# RC522.net
KiCad netlist of a schematic drawn in Altium Designer
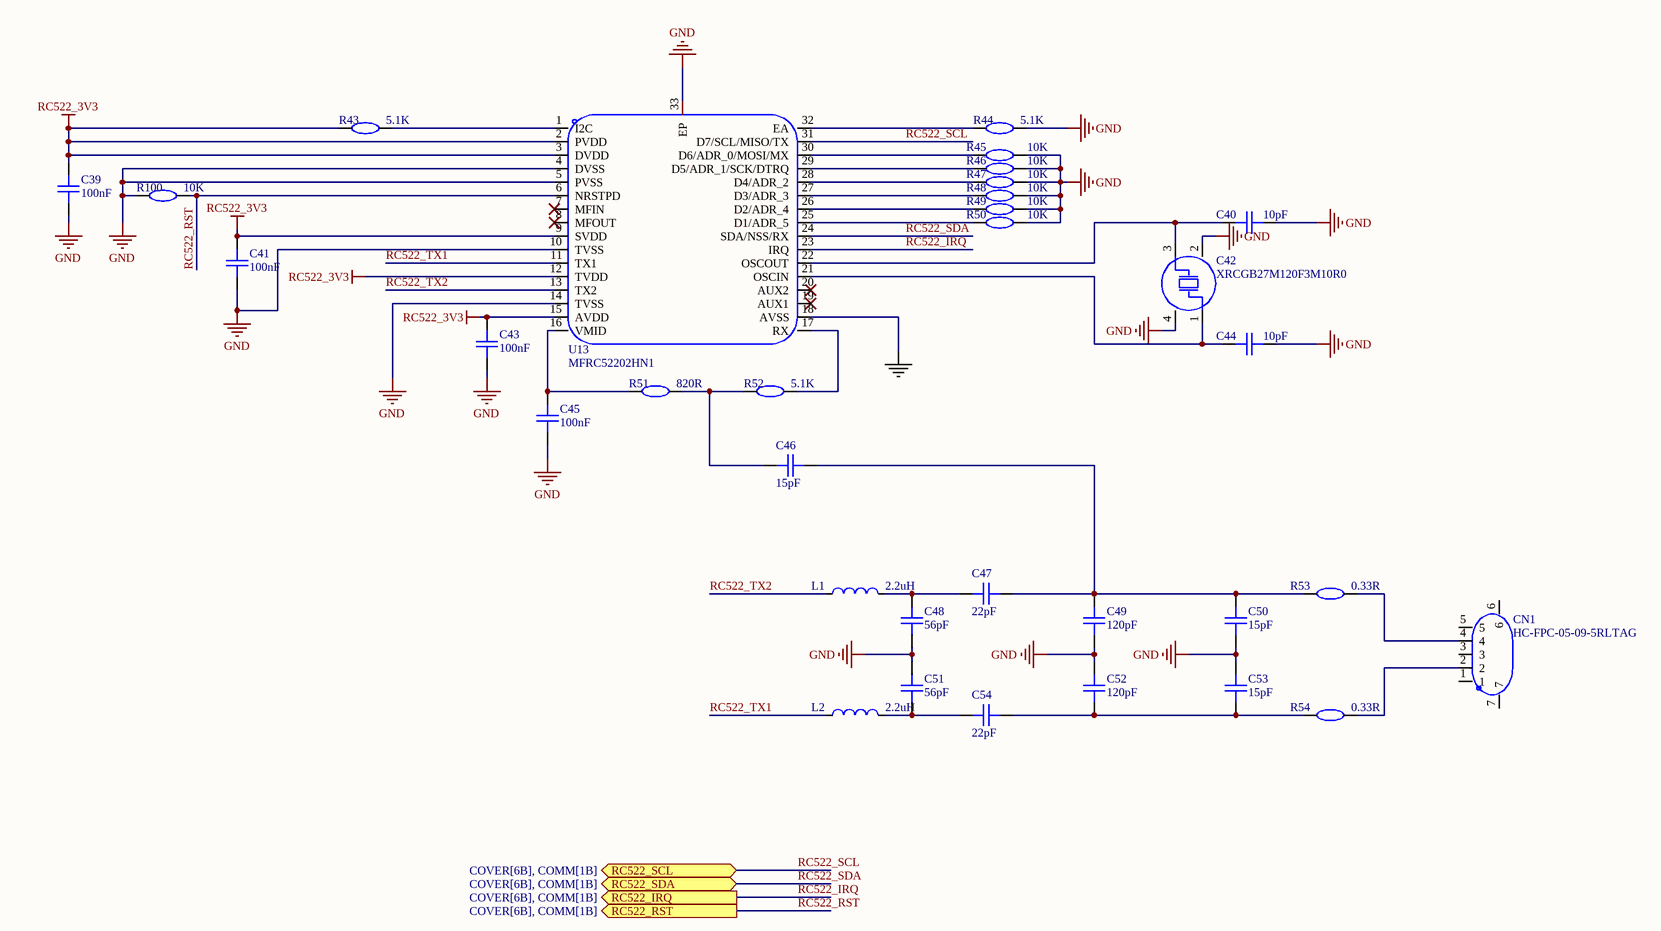
[diagram p0: RC522.SchDoc]

(export (version "E")
  (design (tool "Eeschema 10.0.6"))
  (components
    (comp (ref "C39")
      (value "100nF")
      (footprint "C0402")
      (fields (field (name "NAME") "100nF"))
      (libsource (lib "my_library") (part "CAP_0402"))
    )
    (comp (ref "C40")
      (value "10pF")
      (footprint "C0402")
      (fields (field (name "NAME") "10pF"))
      (libsource (lib "my_library") (part "CAP_0402"))
    )
    (comp (ref "C41")
      (value "100nF")
      (footprint "C0402")
      (fields (field (name "NAME") "100nF"))
      (libsource (lib "my_library") (part "CAP_0402"))
    )
    (comp (ref "C42")
      (value "XRCGB27M120F3M10R0")
      (footprint "CRYSTAL-SMD_4P-L2.0-W1.6-BL-B")
      (fields (field (name "NAME") "XRCGB27M120F3M10R0"))
      (libsource (lib "my_library") (part "XRCGB27M120F3M10R0"))
    )
    (comp (ref "C43")
      (value "100nF")
      (footprint "C0402")
      (fields (field (name "NAME") "100nF"))
      (libsource (lib "my_library") (part "CAP_0402"))
    )
    (comp (ref "C44")
      (value "10pF")
      (footprint "C0402")
      (fields (field (name "NAME") "10pF"))
      (libsource (lib "my_library") (part "CAP_0402"))
    )
    (comp (ref "C45")
      (value "100nF")
      (footprint "C0402")
      (fields (field (name "NAME") "100nF"))
      (libsource (lib "my_library") (part "CAP_0402"))
    )
    (comp (ref "C46")
      (value "15pF")
      (footprint "C0402")
      (fields (field (name "NAME") "15pF"))
      (libsource (lib "my_library") (part "CAP_0402"))
    )
    (comp (ref "C47")
      (value "22pF")
      (footprint "C0402")
      (fields (field (name "NAME") "22pF"))
      (libsource (lib "my_library") (part "CAP_0402"))
    )
    (comp (ref "C48")
      (value "56pF")
      (footprint "C0402")
      (fields (field (name "NAME") "56pF"))
      (libsource (lib "my_library") (part "CAP_0402"))
    )
    (comp (ref "C49")
      (value "120pF")
      (footprint "C0402")
      (fields (field (name "NAME") "120pF"))
      (libsource (lib "my_library") (part "CAP_0402"))
    )
    (comp (ref "C50")
      (value "15pF")
      (footprint "C0402")
      (fields (field (name "NAME") "15pF"))
      (libsource (lib "my_library") (part "CAP_0402"))
    )
    (comp (ref "C51")
      (value "56pF")
      (footprint "C0402")
      (fields (field (name "NAME") "56pF"))
      (libsource (lib "my_library") (part "CAP_0402"))
    )
    (comp (ref "C52")
      (value "120pF")
      (footprint "C0402")
      (fields (field (name "NAME") "120pF"))
      (libsource (lib "my_library") (part "CAP_0402"))
    )
    (comp (ref "C53")
      (value "15pF")
      (footprint "C0402")
      (fields (field (name "NAME") "15pF"))
      (libsource (lib "my_library") (part "CAP_0402"))
    )
    (comp (ref "C54")
      (value "22pF")
      (footprint "C0402")
      (fields (field (name "NAME") "22pF"))
      (libsource (lib "my_library") (part "CAP_0402"))
    )
    (comp (ref "CN1")
      (value "HC-FPC-05-09-5RLTAG")
      (footprint "CONN-SMD_5P-P0.50_HCTL_HC-FPC-05-09-5RLTAG")
      (fields (field (name "MANUFACTURER") "HCTL(华灿天禄)") (field (name "NAME") "HC-FPC-05-09-5RLTAG"))
      (libsource (lib "my_library") (part "HC-FPC-05-09-5RLTAG"))
    )
    (comp (ref "L1")
      (value "2.2uH")
      (footprint "L0603")
      (fields (field (name "NAME") "2.2uH"))
      (libsource (lib "my_library") (part "L_0603"))
    )
    (comp (ref "L2")
      (value "2.2uH")
      (footprint "L0603")
      (fields (field (name "NAME") "2.2uH"))
      (libsource (lib "my_library") (part "L_0603"))
    )
    (comp (ref "R43")
      (value "5.1K")
      (footprint "R0402")
      (fields (field (name "NAME") "5.1K"))
      (libsource (lib "my_library") (part "Res_0402"))
    )
    (comp (ref "R44")
      (value "5.1K")
      (footprint "R0402")
      (fields (field (name "NAME") "5.1K"))
      (libsource (lib "my_library") (part "Res_0402"))
    )
    (comp (ref "R45")
      (value "10K")
      (footprint "R0402")
      (fields (field (name "NAME") "10K"))
      (libsource (lib "my_library") (part "Res_0402"))
    )
    (comp (ref "R46")
      (value "10K")
      (footprint "R0402")
      (fields (field (name "NAME") "10K"))
      (libsource (lib "my_library") (part "Res_0402"))
    )
    (comp (ref "R47")
      (value "10K")
      (footprint "R0402")
      (fields (field (name "NAME") "10K"))
      (libsource (lib "my_library") (part "Res_0402"))
    )
    (comp (ref "R48")
      (value "10K")
      (footprint "R0402")
      (fields (field (name "NAME") "10K"))
      (libsource (lib "my_library") (part "Res_0402"))
    )
    (comp (ref "R49")
      (value "10K")
      (footprint "R0402")
      (fields (field (name "NAME") "10K"))
      (libsource (lib "my_library") (part "Res_0402"))
    )
    (comp (ref "R50")
      (value "10K")
      (footprint "R0402")
      (fields (field (name "NAME") "10K"))
      (libsource (lib "my_library") (part "Res_0402"))
    )
    (comp (ref "R51")
      (value "820R")
      (footprint "R0402")
      (fields (field (name "NAME") "820R"))
      (libsource (lib "my_library") (part "Res_0402"))
    )
    (comp (ref "R52")
      (value "5.1K")
      (footprint "R0402")
      (fields (field (name "NAME") "5.1K"))
      (libsource (lib "my_library") (part "Res_0402"))
    )
    (comp (ref "R53")
      (value "0.33R")
      (footprint "R0402")
      (fields (field (name "NAME") "0.33R"))
      (libsource (lib "my_library") (part "Res_0402"))
    )
    (comp (ref "R54")
      (value "0.33R")
      (footprint "R0402")
      (fields (field (name "NAME") "0.33R"))
      (libsource (lib "my_library") (part "Res_0402"))
    )
    (comp (ref "R100")
      (value "10K")
      (footprint "R0402")
      (fields (field (name "NAME") "10K"))
      (libsource (lib "my_library") (part "Res_0402"))
    )
    (comp (ref "U13")
      (value "MFRC52202HN1")
      (footprint "HVQFN-32_L5.0-W5.0-P0.50-TL-EP3.1")
      (fields (field (name "MANUFACTURER") "NXP(恩智浦)") (field (name "NAME") "MFRC52202HN1"))
      (libsource (lib "my_library") (part "MFRC52202HN1"))
    )
  )
  (nets
    (net (code "1") (name "/RC522_IRQ") (class "Default")
      (node (ref "U13") (pin "23") (pinfunction "IRQ_23") (pintype "passive"))
    )
    (net (code "2") (name "/RC522_RST") (class "Default")
      (node (ref "R100") (pin "2") (pinfunction "2_2") (pintype "passive"))
      (node (ref "U13") (pin "6") (pinfunction "NRSTPD_6") (pintype "passive"))
    )
    (net (code "3") (name "/RC522_SCL") (class "Default")
      (node (ref "U13") (pin "31") (pinfunction "D7/SCL/MISO/TX_31") (pintype "passive"))
    )
    (net (code "4") (name "/RC522_SDA") (class "Default")
      (node (ref "U13") (pin "24") (pinfunction "SDA/NSS/RX_24") (pintype "passive"))
    )
    (net (code "5") (name "/RC522_TX1") (class "Default")
      (node (ref "L2") (pin "1") (pinfunction "1_1") (pintype "passive"))
      (node (ref "U13") (pin "11") (pinfunction "TX1_11") (pintype "passive"))
    )
    (net (code "6") (name "/RC522_TX2") (class "Default")
      (node (ref "L1") (pin "1") (pinfunction "1_1") (pintype "passive"))
      (node (ref "U13") (pin "13") (pinfunction "TX2_13") (pintype "passive"))
    )
    (net (code "7") (name "GND") (class "Default")
      (node (ref "C39") (pin "1") (pinfunction "1_1") (pintype "passive"))
      (node (ref "C40") (pin "1") (pinfunction "1_1") (pintype "passive"))
      (node (ref "C41") (pin "1") (pinfunction "1_1") (pintype "passive"))
      (node (ref "C42") (pin "2") (pinfunction "GND_2") (pintype "passive"))
      (node (ref "C42") (pin "4") (pinfunction "GND_4") (pintype "passive"))
      (node (ref "C43") (pin "1") (pinfunction "1_1") (pintype "passive"))
      (node (ref "C44") (pin "1") (pinfunction "1_1") (pintype "passive"))
      (node (ref "C45") (pin "1") (pinfunction "1_1") (pintype "passive"))
      (node (ref "C48") (pin "2") (pinfunction "2_2") (pintype "passive"))
      (node (ref "C49") (pin "1") (pinfunction "1_1") (pintype "passive"))
      (node (ref "C50") (pin "2") (pinfunction "2_2") (pintype "passive"))
      (node (ref "C51") (pin "1") (pinfunction "1_1") (pintype "passive"))
      (node (ref "C52") (pin "2") (pinfunction "2_2") (pintype "passive"))
      (node (ref "C53") (pin "1") (pinfunction "1_1") (pintype "passive"))
      (node (ref "R100") (pin "1") (pinfunction "1_1") (pintype "passive"))
      (node (ref "R44") (pin "2") (pinfunction "2_2") (pintype "passive"))
      (node (ref "R45") (pin "2") (pinfunction "2_2") (pintype "passive"))
      (node (ref "R46") (pin "2") (pinfunction "2_2") (pintype "passive"))
      (node (ref "R47") (pin "2") (pinfunction "2_2") (pintype "passive"))
      (node (ref "R48") (pin "2") (pinfunction "2_2") (pintype "passive"))
      (node (ref "R49") (pin "2") (pinfunction "2_2") (pintype "passive"))
      (node (ref "R50") (pin "2") (pinfunction "2_2") (pintype "passive"))
      (node (ref "U13") (pin "10") (pinfunction "TVSS_10") (pintype "passive"))
      (node (ref "U13") (pin "14") (pinfunction "TVSS_14") (pintype "passive"))
      (node (ref "U13") (pin "18") (pinfunction "AVSS_18") (pintype "passive"))
      (node (ref "U13") (pin "33") (pinfunction "EP_33") (pintype "passive"))
      (node (ref "U13") (pin "4") (pinfunction "DVSS_4") (pintype "passive"))
      (node (ref "U13") (pin "5") (pinfunction "PVSS_5") (pintype "passive"))
    )
    (net (code "8") (name "Net-(C42-OSC1)") (class "Default")
      (node (ref "C42") (pin "1") (pinfunction "OSC1_1") (pintype "passive"))
      (node (ref "C44") (pin "2") (pinfunction "2_2") (pintype "passive"))
      (node (ref "U13") (pin "21") (pinfunction "OSCIN_21") (pintype "passive"))
    )
    (net (code "9") (name "Net-(C42-OSC2)") (class "Default")
      (node (ref "C40") (pin "2") (pinfunction "2_2") (pintype "passive"))
      (node (ref "C42") (pin "3") (pinfunction "OSC2_3") (pintype "passive"))
      (node (ref "U13") (pin "22") (pinfunction "OSCOUT_22") (pintype "passive"))
    )
    (net (code "10") (name "Net-(C46-Pad1)") (class "Default")
      (node (ref "C46") (pin "1") (pinfunction "1_1") (pintype "passive"))
      (node (ref "C47") (pin "2") (pinfunction "2_2") (pintype "passive"))
      (node (ref "C49") (pin "2") (pinfunction "2_2") (pintype "passive"))
      (node (ref "C50") (pin "1") (pinfunction "1_1") (pintype "passive"))
      (node (ref "R53") (pin "1") (pinfunction "1_1") (pintype "passive"))
    )
    (net (code "11") (name "Net-(C46-Pad2)") (class "Default")
      (node (ref "C46") (pin "2") (pinfunction "2_2") (pintype "passive"))
      (node (ref "R51") (pin "2") (pinfunction "2_2") (pintype "passive"))
      (node (ref "R52") (pin "1") (pinfunction "1_1") (pintype "passive"))
    )
    (net (code "12") (name "Net-(C47-Pad1)") (class "Default")
      (node (ref "C47") (pin "1") (pinfunction "1_1") (pintype "passive"))
      (node (ref "C48") (pin "1") (pinfunction "1_1") (pintype "passive"))
      (node (ref "L1") (pin "2") (pinfunction "2_2") (pintype "passive"))
    )
    (net (code "13") (name "Net-(C51-Pad2)") (class "Default")
      (node (ref "C51") (pin "2") (pinfunction "2_2") (pintype "passive"))
      (node (ref "C54") (pin "1") (pinfunction "1_1") (pintype "passive"))
      (node (ref "L2") (pin "2") (pinfunction "2_2") (pintype "passive"))
    )
    (net (code "14") (name "Net-(C52-Pad1)") (class "Default")
      (node (ref "C52") (pin "1") (pinfunction "1_1") (pintype "passive"))
      (node (ref "C53") (pin "2") (pinfunction "2_2") (pintype "passive"))
      (node (ref "C54") (pin "2") (pinfunction "2_2") (pintype "passive"))
      (node (ref "R54") (pin "1") (pinfunction "1_1") (pintype "passive"))
    )
    (net (code "15") (name "Net-(CN1-Pad2)") (class "Default")
      (node (ref "CN1") (pin "2") (pinfunction "2_2") (pintype "passive"))
      (node (ref "R54") (pin "2") (pinfunction "2_2") (pintype "passive"))
    )
    (net (code "16") (name "Net-(CN1-Pad4)") (class "Default")
      (node (ref "CN1") (pin "4") (pinfunction "4_4") (pintype "passive"))
      (node (ref "R53") (pin "2") (pinfunction "2_2") (pintype "passive"))
    )
    (net (code "17") (name "Net-(U13-D1{slash}ADR_5)") (class "Default")
      (node (ref "R50") (pin "1") (pinfunction "1_1") (pintype "passive"))
      (node (ref "U13") (pin "25") (pinfunction "D1/ADR_5_25") (pintype "passive"))
    )
    (net (code "18") (name "Net-(U13-D2{slash}ADR_4)") (class "Default")
      (node (ref "R49") (pin "1") (pinfunction "1_1") (pintype "passive"))
      (node (ref "U13") (pin "26") (pinfunction "D2/ADR_4_26") (pintype "passive"))
    )
    (net (code "19") (name "Net-(U13-D3{slash}ADR_3)") (class "Default")
      (node (ref "R48") (pin "1") (pinfunction "1_1") (pintype "passive"))
      (node (ref "U13") (pin "27") (pinfunction "D3/ADR_3_27") (pintype "passive"))
    )
    (net (code "20") (name "Net-(U13-D4{slash}ADR_2)") (class "Default")
      (node (ref "R47") (pin "1") (pinfunction "1_1") (pintype "passive"))
      (node (ref "U13") (pin "28") (pinfunction "D4/ADR_2_28") (pintype "passive"))
    )
    (net (code "21") (name "Net-(U13-D5{slash}ADR_1{slash}SCK{slash}DTRQ)") (class "Default")
      (node (ref "R46") (pin "1") (pinfunction "1_1") (pintype "passive"))
      (node (ref "U13") (pin "29") (pinfunction "D5/ADR_1/SCK/DTRQ_29") (pintype "passive"))
    )
    (net (code "22") (name "Net-(U13-D6{slash}ADR_0{slash}MOSI{slash}MX)") (class "Default")
      (node (ref "R45") (pin "1") (pinfunction "1_1") (pintype "passive"))
      (node (ref "U13") (pin "30") (pinfunction "D6/ADR_0/MOSI/MX_30") (pintype "passive"))
    )
    (net (code "23") (name "Net-(U13-EA)") (class "Default")
      (node (ref "R44") (pin "1") (pinfunction "1_1") (pintype "passive"))
      (node (ref "U13") (pin "32") (pinfunction "EA_32") (pintype "passive"))
    )
    (net (code "24") (name "Net-(U13-I2C)") (class "Default")
      (node (ref "R43") (pin "2") (pinfunction "2_2") (pintype "passive"))
      (node (ref "U13") (pin "1") (pinfunction "I2C_1") (pintype "passive"))
    )
    (net (code "25") (name "Net-(U13-RX)") (class "Default")
      (node (ref "R52") (pin "2") (pinfunction "2_2") (pintype "passive"))
      (node (ref "U13") (pin "17") (pinfunction "RX_17") (pintype "passive"))
    )
    (net (code "26") (name "Net-(U13-VMID)") (class "Default")
      (node (ref "C45") (pin "2") (pinfunction "2_2") (pintype "passive"))
      (node (ref "R51") (pin "1") (pinfunction "1_1") (pintype "passive"))
      (node (ref "U13") (pin "16") (pinfunction "VMID_16") (pintype "passive"))
    )
    (net (code "27") (name "RC522_3V3") (class "Default")
      (node (ref "C39") (pin "2") (pinfunction "2_2") (pintype "passive"))
      (node (ref "C41") (pin "2") (pinfunction "2_2") (pintype "passive"))
      (node (ref "C43") (pin "2") (pinfunction "2_2") (pintype "passive"))
      (node (ref "R43") (pin "1") (pinfunction "1_1") (pintype "passive"))
      (node (ref "U13") (pin "12") (pinfunction "TVDD_12") (pintype "passive"))
      (node (ref "U13") (pin "15") (pinfunction "AVDD_15") (pintype "passive"))
      (node (ref "U13") (pin "2") (pinfunction "PVDD_2") (pintype "passive"))
      (node (ref "U13") (pin "3") (pinfunction "DVDD_3") (pintype "passive"))
      (node (ref "U13") (pin "9") (pinfunction "SVDD_9") (pintype "passive"))
    )
    (net (code "28") (name "unconnected-(CN1-Pad1)") (class "Default")
      (node (ref "CN1") (pin "1") (pinfunction "1_1") (pintype "passive"))
    )
    (net (code "29") (name "unconnected-(CN1-Pad3)") (class "Default")
      (node (ref "CN1") (pin "3") (pinfunction "3_3") (pintype "passive"))
    )
    (net (code "30") (name "unconnected-(CN1-Pad5)") (class "Default")
      (node (ref "CN1") (pin "5") (pinfunction "5_5") (pintype "passive"))
    )
    (net (code "31") (name "unconnected-(CN1-Pad6)") (class "Default")
      (node (ref "CN1") (pin "6") (pinfunction "6_6") (pintype "passive"))
    )
    (net (code "32") (name "unconnected-(CN1-Pad7)") (class "Default")
      (node (ref "CN1") (pin "7") (pinfunction "7_7") (pintype "passive"))
    )
    (net (code "33") (name "unconnected-(U13-AUX1-Pad19)") (class "Default")
      (node (ref "U13") (pin "19") (pinfunction "AUX1_19") (pintype "passive+no_connect"))
    )
    (net (code "34") (name "unconnected-(U13-AUX2-Pad20)") (class "Default")
      (node (ref "U13") (pin "20") (pinfunction "AUX2_20") (pintype "passive+no_connect"))
    )
    (net (code "35") (name "unconnected-(U13-MFIN-Pad7)") (class "Default")
      (node (ref "U13") (pin "7") (pinfunction "MFIN_7") (pintype "passive+no_connect"))
    )
    (net (code "36") (name "unconnected-(U13-MFOUT-Pad8)") (class "Default")
      (node (ref "U13") (pin "8") (pinfunction "MFOUT_8") (pintype "passive+no_connect"))
    )
  )
)
